# LoRa_G-Dual_v1_0.net
KiCad netlist of a schematic drawn in EAGLE
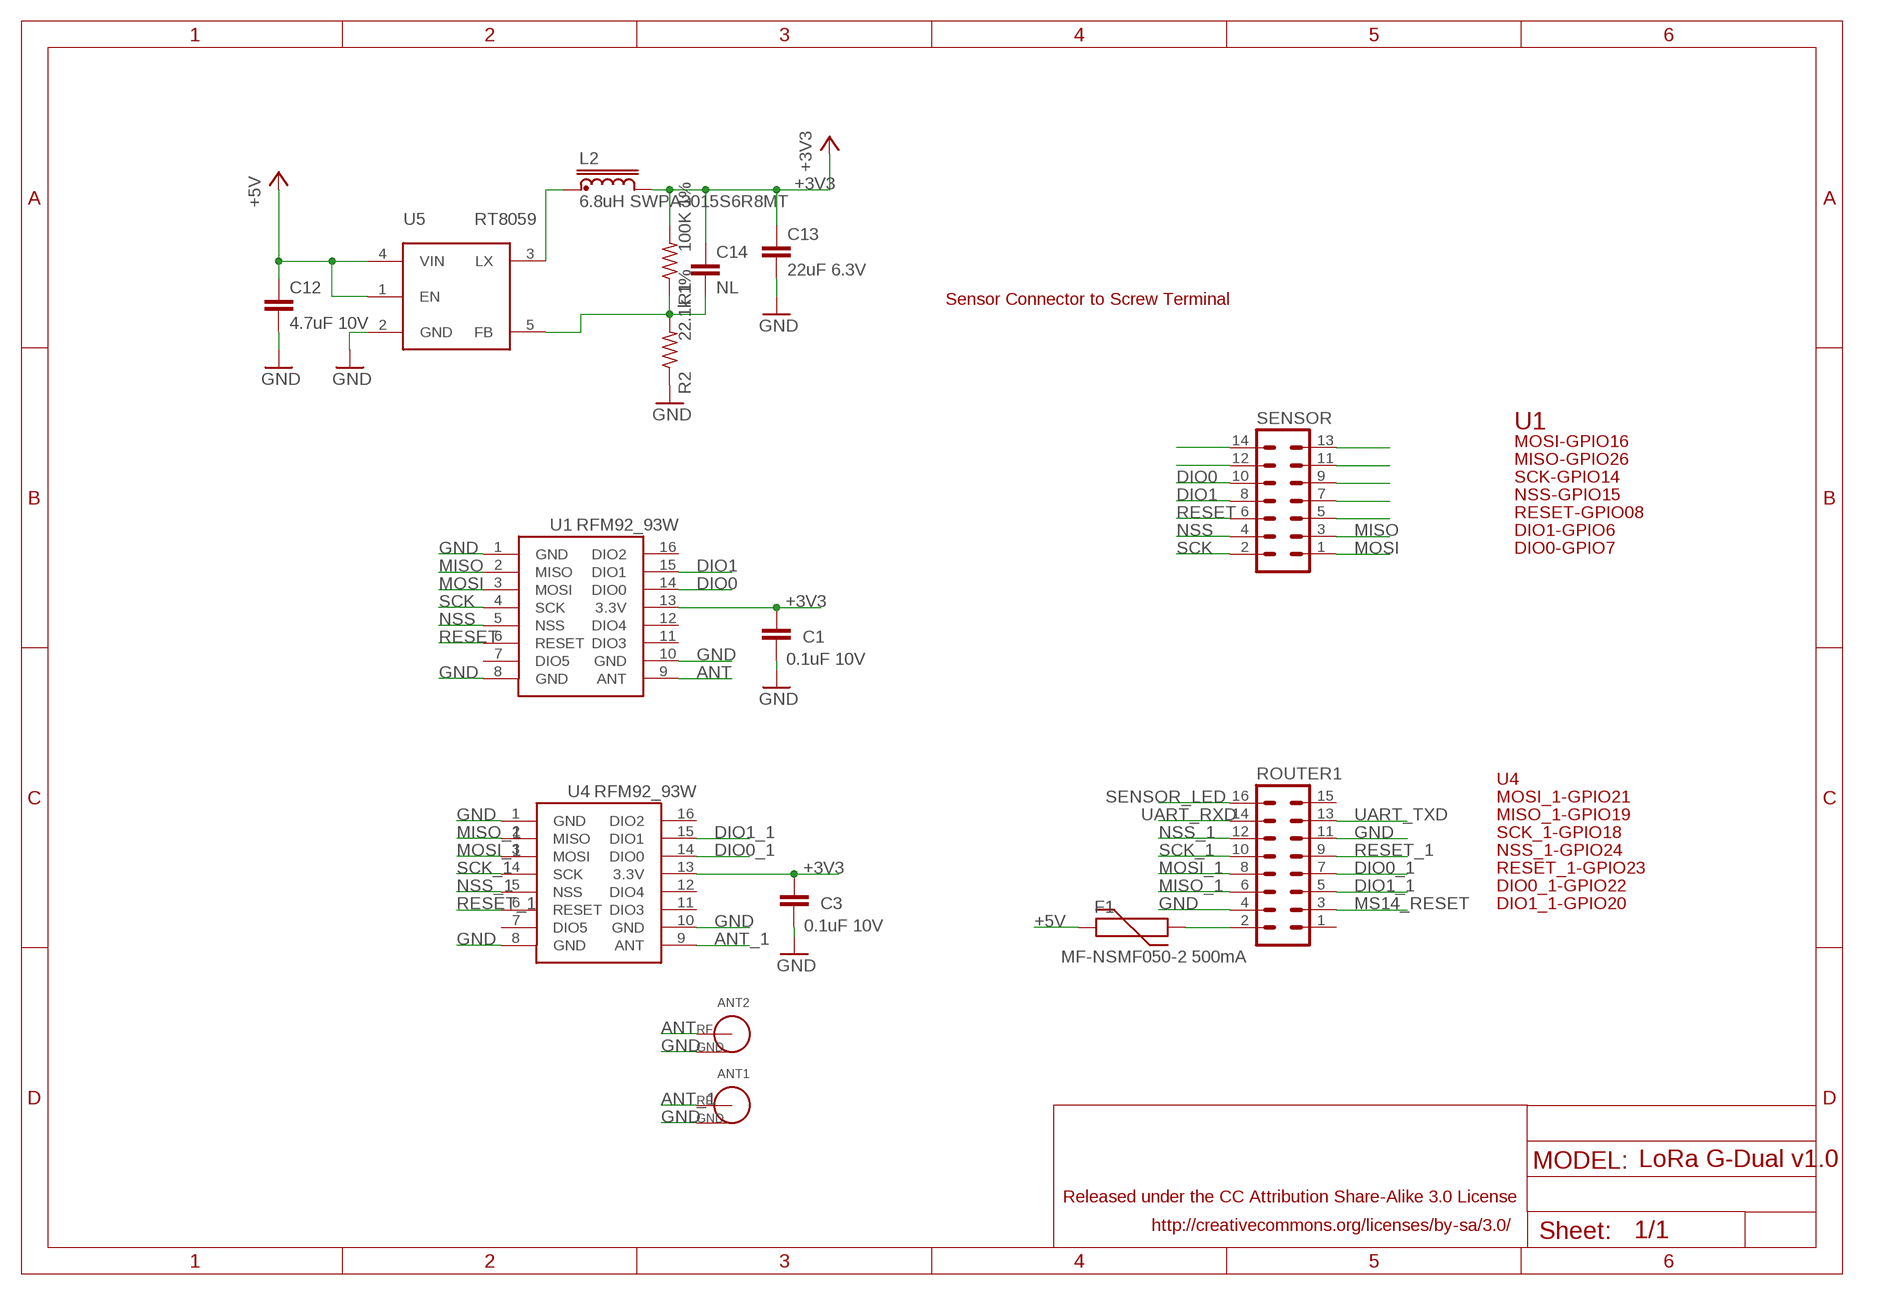
[diagram p0: schematic, sheet 1]

(export (version "E")
  (design (tool "Eeschema 10.0.6"))
  (components
    (comp (ref "ANT1")
      (value "I-PEX")
      (footprint "eagle-import:I-PEX")
      (libsource (lib "eagle-import") (part "I-PEX"))
    )
    (comp (ref "ANT2")
      (value "I-PEX")
      (footprint "eagle-import:I-PEX")
      (libsource (lib "eagle-import") (part "I-PEX"))
    )
    (comp (ref "C1")
      (value "0.1uF 10V")
      (footprint "eagle-import:C0402")
      (libsource (lib "eagle-import") (part "dragino-passive_C-EUC0402"))
    )
    (comp (ref "C3")
      (value "0.1uF 10V")
      (footprint "eagle-import:C0402")
      (libsource (lib "eagle-import") (part "dragino-passive_C-EUC0402"))
    )
    (comp (ref "C12")
      (value "4.7uF 10V")
      (footprint "eagle-import:C0402")
      (libsource (lib "eagle-import") (part "C-EUC0402"))
    )
    (comp (ref "C13")
      (value "22uF 6.3V")
      (footprint "eagle-import:C0603@1")
      (libsource (lib "eagle-import") (part "C-EUC0603"))
    )
    (comp (ref "C14")
      (value "NL")
      (footprint "eagle-import:C0402")
      (libsource (lib "eagle-import") (part "C-EUC0402"))
    )
    (comp (ref "F1")
      (value "MF-NSMF050-2 500mA")
      (footprint "eagle-import:R1206")
      (libsource (lib "eagle-import") (part "FUSE1206"))
    )
    (comp (ref "L2")
      (value "6.8uH SWPA3015S6R8MT")
      (footprint "eagle-import:SWPA3010S")
      (libsource (lib "eagle-import") (part "INDUCTORSWPA3010S"))
    )
    (comp (ref "R1")
      (value "100K 1%")
      (footprint "eagle-import:R0402")
      (libsource (lib "eagle-import") (part "R-US_R0402"))
    )
    (comp (ref "R2")
      (value "22.1k 1%")
      (footprint "eagle-import:R0402")
      (libsource (lib "eagle-import") (part "R-US_R0402"))
    )
    (comp (ref "ROUTER1")
      (value "MA08-2")
      (footprint "eagle-import:MA08-2")
      (libsource (lib "eagle-import") (part "MA08-2"))
    )
    (comp (ref "SENSOR")
      (value "MA07-2")
      (footprint "eagle-import:MA07-2")
      (libsource (lib "eagle-import") (part "MA07-2"))
    )
    (comp (ref "U1")
      (value "RFM92_93W")
      (footprint "eagle-import:RFM92_93W")
      (libsource (lib "eagle-import") (part "RFM92_93W"))
    )
    (comp (ref "U4")
      (value "RFM92_93W")
      (footprint "eagle-import:RFM92_93W")
      (libsource (lib "eagle-import") (part "RFM92_93W"))
    )
    (comp (ref "U5")
      (value "RT8059")
      (footprint "eagle-import:SOT23-5")
      (libsource (lib "eagle-import") (part "RT8059"))
    )
  )
  (nets
    (net (code "1") (name "+3V3") (class "Default")
      (node (ref "C1") (pin "2") (pinfunction "2_2") (pintype "passive"))
      (node (ref "C13") (pin "1") (pinfunction "1_1") (pintype "passive"))
      (node (ref "C14") (pin "1") (pinfunction "1_1") (pintype "passive"))
      (node (ref "C3") (pin "2") (pinfunction "2_2") (pintype "passive"))
      (node (ref "L2") (pin "P$2") (pinfunction "4_P$2") (pintype "passive"))
      (node (ref "R1") (pin "2") (pinfunction "2_2") (pintype "passive"))
      (node (ref "U1") (pin "13") (pinfunction "3.3V_13") (pintype "power_in"))
      (node (ref "U4") (pin "13") (pinfunction "3.3V_13") (pintype "power_in"))
    )
    (net (code "2") (name "+5V") (class "Default")
      (node (ref "C12") (pin "1") (pinfunction "1_1") (pintype "passive"))
      (node (ref "F1") (pin "2") (pinfunction "2_2") (pintype "passive"))
      (node (ref "U5") (pin "1") (pinfunction "EN_1") (pintype "bidirectional"))
      (node (ref "U5") (pin "4") (pinfunction "VIN_4") (pintype "bidirectional"))
    )
    (net (code "3") (name "/ANT") (class "Default")
      (node (ref "ANT2") (pin "SIG") (pinfunction "SIG_SIG") (pintype "passive"))
      (node (ref "U1") (pin "9") (pinfunction "ANT_9") (pintype "bidirectional"))
    )
    (net (code "4") (name "/ANT_1") (class "Default")
      (node (ref "ANT1") (pin "SIG") (pinfunction "SIG_SIG") (pintype "passive"))
      (node (ref "U4") (pin "9") (pinfunction "ANT_9") (pintype "bidirectional"))
    )
    (net (code "5") (name "/DIO0") (class "Default")
      (node (ref "SENSOR") (pin "10") (pinfunction "10_10") (pintype "passive"))
      (node (ref "U1") (pin "14") (pinfunction "DIO0_14") (pintype "bidirectional"))
    )
    (net (code "6") (name "/DIO0_1") (class "Default")
      (node (ref "ROUTER1") (pin "7") (pinfunction "7_7") (pintype "passive"))
      (node (ref "U4") (pin "14") (pinfunction "DIO0_14") (pintype "bidirectional"))
    )
    (net (code "7") (name "/DIO1") (class "Default")
      (node (ref "SENSOR") (pin "8") (pinfunction "8_8") (pintype "passive"))
      (node (ref "U1") (pin "15") (pinfunction "DIO1_15") (pintype "bidirectional"))
    )
    (net (code "8") (name "/DIO1_1") (class "Default")
      (node (ref "ROUTER1") (pin "5") (pinfunction "5_5") (pintype "passive"))
      (node (ref "U4") (pin "15") (pinfunction "DIO1_15") (pintype "bidirectional"))
    )
    (net (code "9") (name "/MISO") (class "Default")
      (node (ref "SENSOR") (pin "3") (pinfunction "3_3") (pintype "passive"))
      (node (ref "U1") (pin "2") (pinfunction "MISO_2") (pintype "bidirectional"))
    )
    (net (code "10") (name "/MISO_1") (class "Default")
      (node (ref "ROUTER1") (pin "6") (pinfunction "6_6") (pintype "passive"))
      (node (ref "U4") (pin "2") (pinfunction "MISO_2") (pintype "bidirectional"))
    )
    (net (code "11") (name "/MOSI") (class "Default")
      (node (ref "SENSOR") (pin "1") (pinfunction "1_1") (pintype "passive"))
      (node (ref "U1") (pin "3") (pinfunction "MOSI_3") (pintype "bidirectional"))
    )
    (net (code "12") (name "/MOSI_1") (class "Default")
      (node (ref "ROUTER1") (pin "8") (pinfunction "8_8") (pintype "passive"))
      (node (ref "U4") (pin "3") (pinfunction "MOSI_3") (pintype "bidirectional"))
    )
    (net (code "13") (name "/MS14_RESET") (class "Default")
      (node (ref "ROUTER1") (pin "3") (pinfunction "3_3") (pintype "passive"))
    )
    (net (code "14") (name "/NSS") (class "Default")
      (node (ref "SENSOR") (pin "4") (pinfunction "4_4") (pintype "passive"))
      (node (ref "U1") (pin "5") (pinfunction "NSS_5") (pintype "bidirectional"))
    )
    (net (code "15") (name "/NSS_1") (class "Default")
      (node (ref "ROUTER1") (pin "12") (pinfunction "12_12") (pintype "passive"))
      (node (ref "U4") (pin "5") (pinfunction "NSS_5") (pintype "bidirectional"))
    )
    (net (code "16") (name "/RESET") (class "Default")
      (node (ref "SENSOR") (pin "6") (pinfunction "6_6") (pintype "passive"))
      (node (ref "U1") (pin "6") (pinfunction "RESET_6") (pintype "bidirectional"))
    )
    (net (code "17") (name "/RESET_1") (class "Default")
      (node (ref "ROUTER1") (pin "9") (pinfunction "9_9") (pintype "passive"))
      (node (ref "U4") (pin "6") (pinfunction "RESET_6") (pintype "bidirectional"))
    )
    (net (code "18") (name "/SCK") (class "Default")
      (node (ref "SENSOR") (pin "2") (pinfunction "2_2") (pintype "passive"))
      (node (ref "U1") (pin "4") (pinfunction "SCK_4") (pintype "bidirectional"))
    )
    (net (code "19") (name "/SCK_1") (class "Default")
      (node (ref "ROUTER1") (pin "10") (pinfunction "10_10") (pintype "passive"))
      (node (ref "U4") (pin "4") (pinfunction "SCK_4") (pintype "bidirectional"))
    )
    (net (code "20") (name "/SENSOR_LED") (class "Default")
      (node (ref "ROUTER1") (pin "16") (pinfunction "16_16") (pintype "passive"))
    )
    (net (code "21") (name "/UART_RXD") (class "Default")
      (node (ref "ROUTER1") (pin "14") (pinfunction "14_14") (pintype "passive"))
    )
    (net (code "22") (name "/UART_TXD") (class "Default")
      (node (ref "ROUTER1") (pin "13") (pinfunction "13_13") (pintype "passive"))
    )
    (net (code "23") (name "GND") (class "Default")
      (node (ref "ANT1") (pin "GND") (pinfunction "GND_GND") (pintype "passive"))
      (node (ref "ANT1") (pin "GND1") (pinfunction "GND_GND1") (pintype "passive"))
      (node (ref "ANT2") (pin "GND") (pinfunction "GND_GND") (pintype "passive"))
      (node (ref "ANT2") (pin "GND1") (pinfunction "GND_GND1") (pintype "passive"))
      (node (ref "C1") (pin "1") (pinfunction "1_1") (pintype "passive"))
      (node (ref "C12") (pin "2") (pinfunction "2_2") (pintype "passive"))
      (node (ref "C13") (pin "2") (pinfunction "2_2") (pintype "passive"))
      (node (ref "C3") (pin "1") (pinfunction "1_1") (pintype "passive"))
      (node (ref "R2") (pin "1") (pinfunction "1_1") (pintype "passive"))
      (node (ref "ROUTER1") (pin "11") (pinfunction "11_11") (pintype "passive"))
      (node (ref "ROUTER1") (pin "4") (pinfunction "4_4") (pintype "passive"))
      (node (ref "U1") (pin "1") (pinfunction "GND_1") (pintype "power_in"))
      (node (ref "U1") (pin "10") (pinfunction "GND_10") (pintype "power_in"))
      (node (ref "U1") (pin "8") (pinfunction "GND_8") (pintype "power_in"))
      (node (ref "U4") (pin "1") (pinfunction "GND_1") (pintype "power_in"))
      (node (ref "U4") (pin "10") (pinfunction "GND_10") (pintype "power_in"))
      (node (ref "U4") (pin "8") (pinfunction "GND_8") (pintype "power_in"))
      (node (ref "U5") (pin "2") (pinfunction "GND_2") (pintype "bidirectional"))
    )
    (net (code "24") (name "Net-(F1-Pad1)") (class "Default")
      (node (ref "F1") (pin "1") (pinfunction "1_1") (pintype "passive"))
      (node (ref "ROUTER1") (pin "2") (pinfunction "2_2") (pintype "passive"))
    )
    (net (code "25") (name "Net-(L2-1)") (class "Default")
      (node (ref "L2") (pin "P$1") (pinfunction "1_P$1") (pintype "passive"))
      (node (ref "U5") (pin "3") (pinfunction "LX_3") (pintype "bidirectional"))
    )
    (net (code "26") (name "Net-(U5-FB)") (class "Default")
      (node (ref "C14") (pin "2") (pinfunction "2_2") (pintype "passive"))
      (node (ref "R1") (pin "1") (pinfunction "1_1") (pintype "passive"))
      (node (ref "R2") (pin "2") (pinfunction "2_2") (pintype "passive"))
      (node (ref "U5") (pin "5") (pinfunction "FB_5") (pintype "bidirectional"))
    )
    (net (code "27") (name "unconnected-(ROUTER1-Pad1)") (class "Default")
      (node (ref "ROUTER1") (pin "1") (pinfunction "1_1") (pintype "passive"))
    )
    (net (code "28") (name "unconnected-(ROUTER1-Pad15)") (class "Default")
      (node (ref "ROUTER1") (pin "15") (pinfunction "15_15") (pintype "passive"))
    )
    (net (code "29") (name "unconnected-(SENSOR-Pad5)") (class "Default")
      (node (ref "SENSOR") (pin "5") (pinfunction "5_5") (pintype "passive"))
    )
    (net (code "30") (name "unconnected-(SENSOR-Pad7)") (class "Default")
      (node (ref "SENSOR") (pin "7") (pinfunction "7_7") (pintype "passive"))
    )
    (net (code "31") (name "unconnected-(SENSOR-Pad9)") (class "Default")
      (node (ref "SENSOR") (pin "9") (pinfunction "9_9") (pintype "passive"))
    )
    (net (code "32") (name "unconnected-(SENSOR-Pad11)") (class "Default")
      (node (ref "SENSOR") (pin "11") (pinfunction "11_11") (pintype "passive"))
    )
    (net (code "33") (name "unconnected-(SENSOR-Pad12)") (class "Default")
      (node (ref "SENSOR") (pin "12") (pinfunction "12_12") (pintype "passive"))
    )
    (net (code "34") (name "unconnected-(SENSOR-Pad13)") (class "Default")
      (node (ref "SENSOR") (pin "13") (pinfunction "13_13") (pintype "passive"))
    )
    (net (code "35") (name "unconnected-(SENSOR-Pad14)") (class "Default")
      (node (ref "SENSOR") (pin "14") (pinfunction "14_14") (pintype "passive"))
    )
    (net (code "36") (name "unconnected-(U1-DIO2-Pad16)") (class "Default")
      (node (ref "U1") (pin "16") (pinfunction "DIO2_16") (pintype "bidirectional"))
    )
    (net (code "37") (name "unconnected-(U1-DIO3-Pad11)") (class "Default")
      (node (ref "U1") (pin "11") (pinfunction "DIO3_11") (pintype "bidirectional"))
    )
    (net (code "38") (name "unconnected-(U1-DIO4-Pad12)") (class "Default")
      (node (ref "U1") (pin "12") (pinfunction "DIO4_12") (pintype "bidirectional"))
    )
    (net (code "39") (name "unconnected-(U1-DIO5-Pad7)") (class "Default")
      (node (ref "U1") (pin "7") (pinfunction "DIO5_7") (pintype "bidirectional"))
    )
    (net (code "40") (name "unconnected-(U4-DIO2-Pad16)") (class "Default")
      (node (ref "U4") (pin "16") (pinfunction "DIO2_16") (pintype "bidirectional"))
    )
    (net (code "41") (name "unconnected-(U4-DIO3-Pad11)") (class "Default")
      (node (ref "U4") (pin "11") (pinfunction "DIO3_11") (pintype "bidirectional"))
    )
    (net (code "42") (name "unconnected-(U4-DIO4-Pad12)") (class "Default")
      (node (ref "U4") (pin "12") (pinfunction "DIO4_12") (pintype "bidirectional"))
    )
    (net (code "43") (name "unconnected-(U4-DIO5-Pad7)") (class "Default")
      (node (ref "U4") (pin "7") (pinfunction "DIO5_7") (pintype "bidirectional"))
    )
  )
)
